# Output.net
KiCad netlist of a schematic drawn in Altium Designer
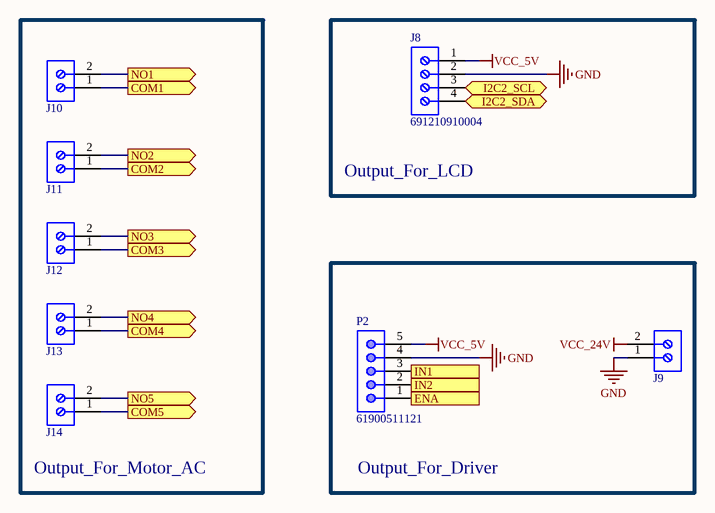
[diagram p0: Output.SchDoc]

(export (version "E")
  (design (tool "Eeschema 10.0.6"))
  (components
    (comp (ref "J8")
      (value "691210910004")
      (footprint "691210910004")
      (description "WR-TBL Serie 2109 Horizontal Entry, Rising Cage Clamp, pitch 2.54mm, 4p")
      (fields (field (name "PUBLISHER") "Wurth Elektronik"))
      (libsource (lib "691322310002.") (part "691210910004"))
    )
    (comp (ref "J9")
      (value "691137710002")
      (footprint "691137710002")
      (description "WR-TBL Series 1377 Horizontal Entry, Through Hole, pitch 5mm, 2p")
      (fields (field (name "MANUFACTURER") "Wurth Elektronik"))
      (libsource (lib "Altium_WR-TBL (rev22a)") (part "691137710002"))
    )
    (comp (ref "J10")
      (value "691137710002")
      (footprint "691137710002")
      (description "WR-TBL Series 1377 Horizontal Entry, Through Hole, pitch 5mm, 2p")
      (fields (field (name "MANUFACTURER") "Wurth Elektronik"))
      (libsource (lib "Altium_WR-TBL (rev22a)") (part "691137710002"))
    )
    (comp (ref "J11")
      (value "691137710002")
      (footprint "691137710002")
      (description "WR-TBL Series 1377 Horizontal Entry, Through Hole, pitch 5mm, 2p")
      (fields (field (name "MANUFACTURER") "Wurth Elektronik"))
      (libsource (lib "Altium_WR-TBL (rev22a)") (part "691137710002"))
    )
    (comp (ref "J12")
      (value "691137710002")
      (footprint "691137710002")
      (description "WR-TBL Series 1377 Horizontal Entry, Through Hole, pitch 5mm, 2p")
      (fields (field (name "MANUFACTURER") "Wurth Elektronik"))
      (libsource (lib "Altium_WR-TBL (rev22a)") (part "691137710002"))
    )
    (comp (ref "J13")
      (value "691137710002")
      (footprint "691137710002")
      (description "WR-TBL Series 1377 Horizontal Entry, Through Hole, pitch 5mm, 2p")
      (fields (field (name "MANUFACTURER") "Wurth Elektronik"))
      (libsource (lib "Altium_WR-TBL (rev22a)") (part "691137710002"))
    )
    (comp (ref "J14")
      (value "691137710002")
      (footprint "691137710002")
      (description "WR-TBL Series 1377 Horizontal Entry, Through Hole, pitch 5mm, 2p")
      (fields (field (name "MANUFACTURER") "Wurth Elektronik"))
      (libsource (lib "Altium_WR-TBL (rev22a)") (part "691137710002"))
    )
    (comp (ref "P2")
      (value "61900511121")
      (footprint "61900511121")
      (description "WR-WTB THT Male Vertical Locking Header, pitch 2.54mm, 5p")
      (fields (field (name "PUBLISHER") "Wurth Elektronik"))
      (libsource (lib "653008114822_Altium_WR-WTB_rev20a") (part "61900511121"))
    )
  )
  (nets
    (net (code "1") (name "/COM1") (class "Default")
      (node (ref "J10") (pin "1") (pinfunction "1_1") (pintype "passive"))
    )
    (net (code "2") (name "/COM2") (class "Default")
      (node (ref "J11") (pin "1") (pinfunction "1_1") (pintype "passive"))
    )
    (net (code "3") (name "/COM3") (class "Default")
      (node (ref "J12") (pin "1") (pinfunction "1_1") (pintype "passive"))
    )
    (net (code "4") (name "/COM4") (class "Default")
      (node (ref "J13") (pin "1") (pinfunction "1_1") (pintype "passive"))
    )
    (net (code "5") (name "/COM5") (class "Default")
      (node (ref "J14") (pin "1") (pinfunction "1_1") (pintype "passive"))
    )
    (net (code "6") (name "/ENA") (class "Default")
      (node (ref "P2") (pin "1") (pinfunction "1_1") (pintype "passive"))
    )
    (net (code "7") (name "/I2C2_SCL") (class "Default")
      (node (ref "J8") (pin "3") (pinfunction "3_3") (pintype "passive"))
    )
    (net (code "8") (name "/I2C2_SDA") (class "Default")
      (node (ref "J8") (pin "4") (pinfunction "4_4") (pintype "passive"))
    )
    (net (code "9") (name "/IN1") (class "Default")
      (node (ref "P2") (pin "3") (pinfunction "3_3") (pintype "passive"))
    )
    (net (code "10") (name "/IN2") (class "Default")
      (node (ref "P2") (pin "2") (pinfunction "2_2") (pintype "passive"))
    )
    (net (code "11") (name "/NO1") (class "Default")
      (node (ref "J10") (pin "2") (pinfunction "2_2") (pintype "passive"))
    )
    (net (code "12") (name "/NO2") (class "Default")
      (node (ref "J11") (pin "2") (pinfunction "2_2") (pintype "passive"))
    )
    (net (code "13") (name "/NO3") (class "Default")
      (node (ref "J12") (pin "2") (pinfunction "2_2") (pintype "passive"))
    )
    (net (code "14") (name "/NO4") (class "Default")
      (node (ref "J13") (pin "2") (pinfunction "2_2") (pintype "passive"))
    )
    (net (code "15") (name "/NO5") (class "Default")
      (node (ref "J14") (pin "2") (pinfunction "2_2") (pintype "passive"))
    )
    (net (code "16") (name "GND") (class "Default")
      (node (ref "J8") (pin "2") (pinfunction "2_2") (pintype "passive"))
      (node (ref "J9") (pin "1") (pinfunction "1_1") (pintype "passive"))
      (node (ref "P2") (pin "4") (pinfunction "4_4") (pintype "passive"))
    )
    (net (code "17") (name "VCC_5V") (class "Default")
      (node (ref "J8") (pin "1") (pinfunction "1_1") (pintype "passive"))
      (node (ref "P2") (pin "5") (pinfunction "5_5") (pintype "passive"))
    )
    (net (code "18") (name "VCC_24V") (class "Default")
      (node (ref "J9") (pin "2") (pinfunction "2_2") (pintype "passive"))
    )
  )
)
